# SensorPH.net
KiCad netlist of a schematic drawn in Altium Designer
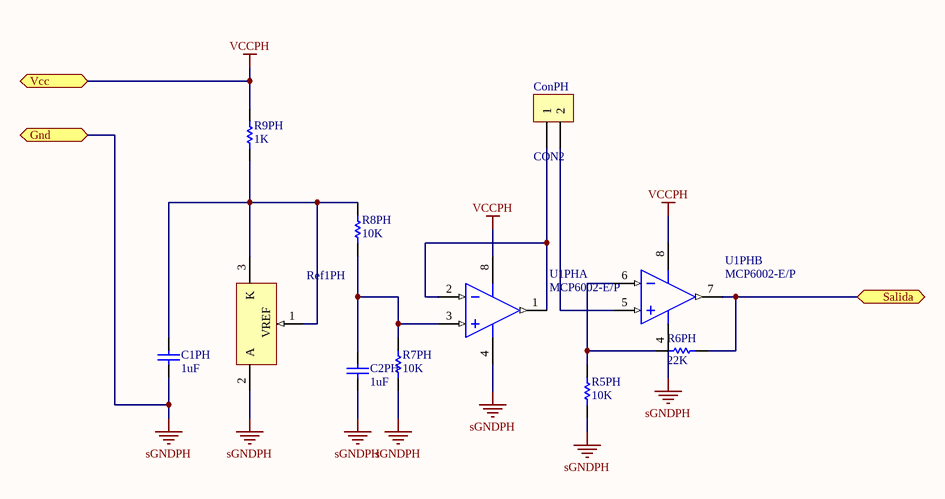
[diagram p0: SensorPH.SchDoc]

(export (version "E")
  (design (tool "Eeschema 10.0.6"))
  (components
    (comp (ref "C1PH")
      (value "1uF")
      (footprint "CAPPOL100")
      (description "Capacitor")
      (libsource (lib "IDTILab") (part "CAP"))
    )
    (comp (ref "C2PH")
      (value "1uF")
      (footprint "CAPPOL100")
      (description "Capacitor")
      (libsource (lib "IDTILab") (part "CAP"))
    )
    (comp (ref "ConPH")
      (value "CON2")
      (footprint "BORNERA2 - T")
      (description "Conector 2")
      (libsource (lib "IDTILab") (part "CON2"))
    )
    (comp (ref "R5PH")
      (value "10K")
      (footprint "RES300")
      (description "Resistencia")
      (libsource (lib "IDTILab") (part "RES"))
    )
    (comp (ref "R6PH")
      (value "22K")
      (footprint "RES300")
      (description "Resistencia")
      (libsource (lib "IDTILab") (part "RES"))
    )
    (comp (ref "R7PH")
      (value "10K")
      (footprint "RES300")
      (description "Resistencia")
      (libsource (lib "IDTILab") (part "RES"))
    )
    (comp (ref "R8PH")
      (value "10K")
      (footprint "RES300")
      (description "Resistencia")
      (libsource (lib "IDTILab") (part "RES"))
    )
    (comp (ref "R9PH")
      (value "1K")
      (footprint "RES300")
      (description "Resistencia")
      (libsource (lib "IDTILab") (part "RES"))
    )
    (comp (ref "Ref1PH")
      (value "TL431ACLP")
      (footprint "LP03")
      (description "Adjustable Precision Shunt Regulator")
      (fields (field (name "PUBLISHER") "Altium Limited"))
      (libsource (lib "TI Power Mgt Voltage Regulator") (part "TL431ACLP"))
    )
    (comp (ref "U1PH")
      (value "MCP6002-E/P")
      (footprint "DIP8B")
      (description "1 MHz, Low-Power Operational Amplifier, 8-Pin PDIP, Extended Temperature")
      (fields (field (name "PUBLISHER") "Altium Limited"))
      (libsource (lib "Microchip Linear Devices") (part "MCP6002-E/P"))
    )
  )
  (nets
    (net (code "1") (name "/Salida") (class "Default")
      (node (ref "R6PH") (pin "1") (pinfunction "1_1") (pintype "passive"))
      (node (ref "U1PH") (pin "7") (pinfunction "VOUTB_7") (pintype "output"))
    )
    (net (code "2") (name "Net-(Ref1PH-K)") (class "Default")
      (node (ref "C1PH") (pin "2") (pinfunction "2_2") (pintype "passive"))
      (node (ref "R8PH") (pin "2") (pinfunction "2_2") (pintype "passive"))
      (node (ref "R9PH") (pin "1") (pinfunction "1_1") (pintype "passive"))
      (node (ref "Ref1PH") (pin "1") (pinfunction "VREF_1") (pintype "input"))
      (node (ref "Ref1PH") (pin "3") (pinfunction "K_3") (pintype "power_in"))
    )
    (net (code "3") (name "Net-(U1PHA-VINA+)") (class "Default")
      (node (ref "C2PH") (pin "2") (pinfunction "2_2") (pintype "passive"))
      (node (ref "R7PH") (pin "2") (pinfunction "2_2") (pintype "passive"))
      (node (ref "R8PH") (pin "1") (pinfunction "1_1") (pintype "passive"))
      (node (ref "U1PH") (pin "3") (pinfunction "VINA+_3") (pintype "input"))
    )
    (net (code "4") (name "Net-(U1PHA-VINA-)") (class "Default")
      (node (ref "ConPH") (pin "1") (pinfunction "1_1") (pintype "passive"))
      (node (ref "U1PH") (pin "1") (pinfunction "VOUTA_1") (pintype "output"))
      (node (ref "U1PH") (pin "2") (pinfunction "VINA-_2") (pintype "input"))
    )
    (net (code "5") (name "Net-(U1PHB-VINB+)") (class "Default")
      (node (ref "ConPH") (pin "2") (pinfunction "2_2") (pintype "passive"))
      (node (ref "U1PH") (pin "5") (pinfunction "VINB+_5") (pintype "input"))
    )
    (net (code "6") (name "Net-(U1PHB-VINB-)") (class "Default")
      (node (ref "R5PH") (pin "2") (pinfunction "2_2") (pintype "passive"))
      (node (ref "R6PH") (pin "2") (pinfunction "2_2") (pintype "passive"))
      (node (ref "U1PH") (pin "6") (pinfunction "VINB-_6") (pintype "input"))
    )
    (net (code "7") (name "VCCPH") (class "Default")
      (node (ref "R9PH") (pin "2") (pinfunction "2_2") (pintype "passive"))
      (node (ref "U1PH") (pin "8") (pinfunction "VDD_8") (pintype "power_in"))
    )
    (net (code "8") (name "sGNDPH") (class "Default")
      (node (ref "C1PH") (pin "1") (pinfunction "1_1") (pintype "passive"))
      (node (ref "C2PH") (pin "1") (pinfunction "1_1") (pintype "passive"))
      (node (ref "R5PH") (pin "1") (pinfunction "1_1") (pintype "passive"))
      (node (ref "R7PH") (pin "1") (pinfunction "1_1") (pintype "passive"))
      (node (ref "Ref1PH") (pin "2") (pinfunction "A_2") (pintype "power_in"))
      (node (ref "U1PH") (pin "4") (pinfunction "VSS_4") (pintype "power_in"))
    )
  )
)
